# PCB_Schematic.net
KiCad netlist of a schematic drawn in Altium Designer
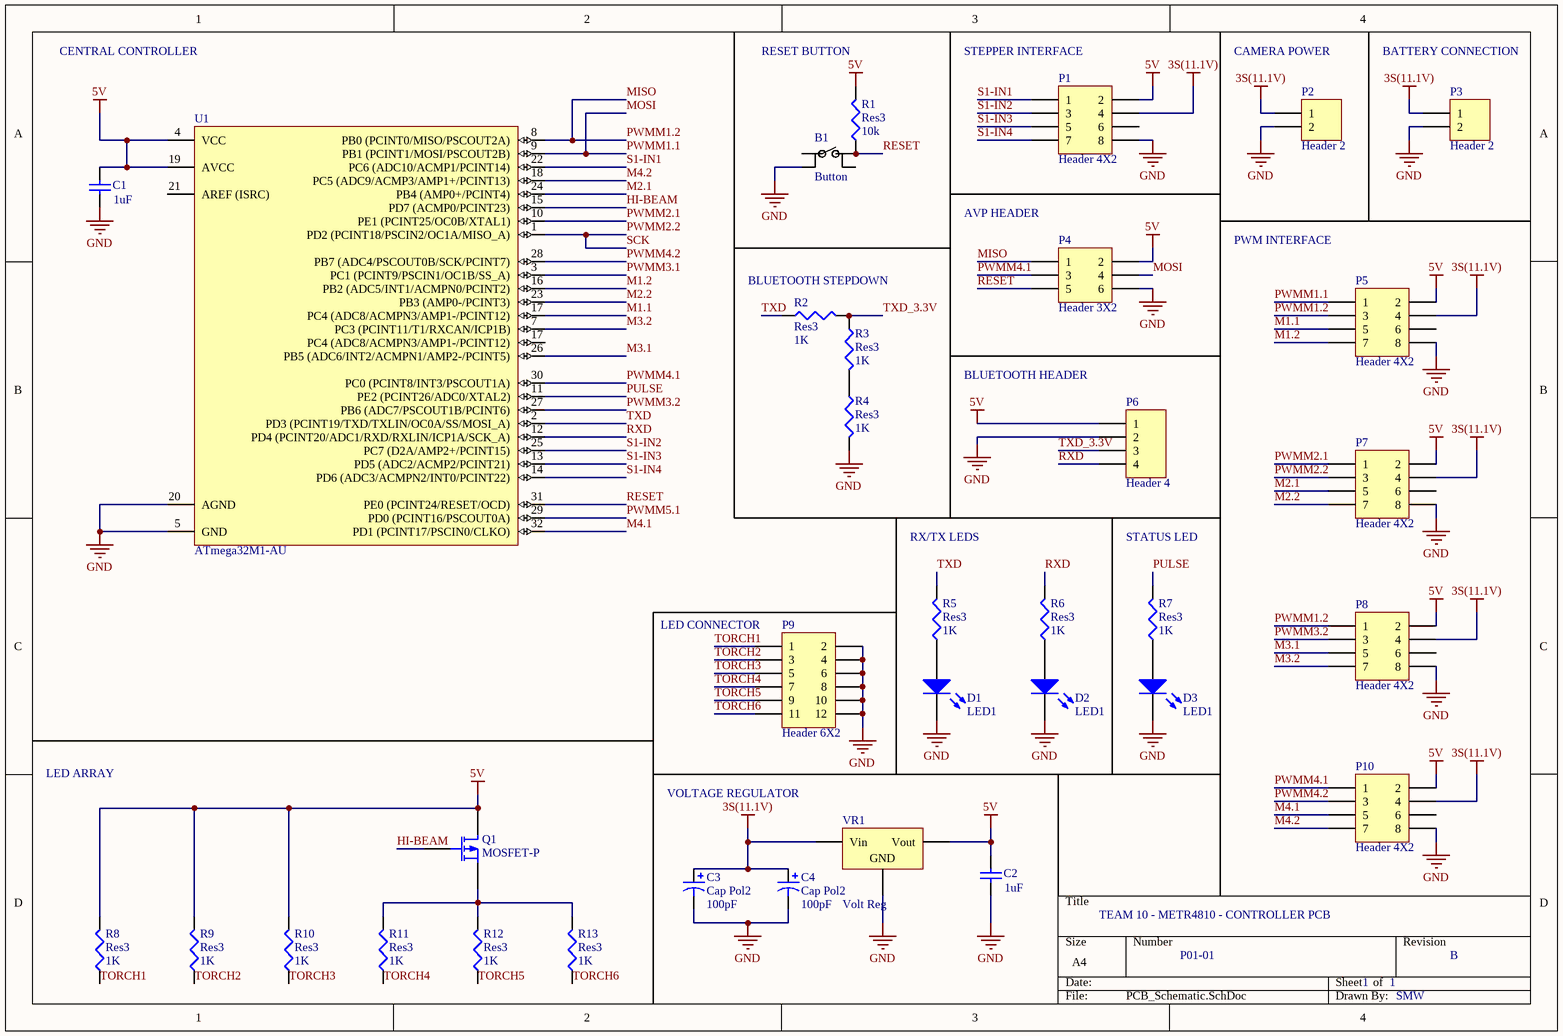
[diagram p0: PCB_Schematic.SchDoc]

(export (version "E")
  (design (tool "Eeschema 10.0.6"))
  (components
    (comp (ref "B1")
      (value "Button")
      (footprint "SMT Tactile Button")
      (libsource (lib "WillsSchematicLibrary") (part "Switch"))
    )
    (comp (ref "C1")
      (value "1uF")
      (footprint "1608[0603]")
      (description "Capacitor")
      (fields (field (name "Comment") "Cap") (field (name "PUBLISHER") "Altium Limited"))
      (libsource (lib "Miscellaneous Devices") (part "Cap"))
    )
    (comp (ref "C2")
      (value "1uF")
      (footprint "1608[0603]")
      (description "Capacitor")
      (fields (field (name "Comment") "Cap") (field (name "PUBLISHER") "Altium Limited"))
      (libsource (lib "Miscellaneous Devices") (part "Cap"))
    )
    (comp (ref "C3")
      (value "Cap Pol2")
      (footprint "CAPAE9983X105M")
      (description "Polarized Capacitor (Axial)")
      (fields (field (name "ALTIUM_VALUE") "100pF") (field (name "PUBLISHER") "Altium Limited"))
      (libsource (lib "Miscellaneous Devices") (part "Cap Pol2"))
    )
    (comp (ref "C4")
      (value "Cap Pol2")
      (footprint "CAPAE9983X105M")
      (description "Polarized Capacitor (Axial)")
      (fields (field (name "ALTIUM_VALUE") "100pF") (field (name "PUBLISHER") "Altium Limited"))
      (libsource (lib "Miscellaneous Devices") (part "Cap Pol2"))
    )
    (comp (ref "D1")
      (value "LED1")
      (footprint "L0603")
      (description "Typical RED GaAs LED")
      (fields (field (name "PUBLISHER") "Altium Limited"))
      (libsource (lib "Miscellaneous Devices") (part "LED1"))
    )
    (comp (ref "D2")
      (value "LED1")
      (footprint "L0603")
      (description "Typical RED GaAs LED")
      (fields (field (name "PUBLISHER") "Altium Limited"))
      (libsource (lib "Miscellaneous Devices") (part "LED1"))
    )
    (comp (ref "D3")
      (value "LED1")
      (footprint "L0603")
      (description "Typical RED GaAs LED")
      (fields (field (name "PUBLISHER") "Altium Limited"))
      (libsource (lib "Miscellaneous Devices") (part "LED1"))
    )
    (comp (ref "P1")
      (value "Header 4X2")
      (footprint "HDR2X4")
      (description "Header, 4-Pin, Dual row")
      (fields (field (name "PUBLISHER") "Altium Limited"))
      (libsource (lib "Miscellaneous Connectors") (part "Header 4X2"))
    )
    (comp (ref "P2")
      (value "Header 2")
      (footprint "HDR1X2")
      (description "Header, 2-Pin")
      (fields (field (name "PUBLISHER") "Altium Limited"))
      (libsource (lib "Miscellaneous Connectors") (part "Header 2"))
    )
    (comp (ref "P3")
      (value "Header 2")
      (footprint "HDR1X2")
      (description "Header, 2-Pin")
      (fields (field (name "PUBLISHER") "Altium Limited"))
      (libsource (lib "Miscellaneous Connectors") (part "Header 2"))
    )
    (comp (ref "P4")
      (value "Header 3X2")
      (footprint "HDR2X3")
      (description "Header, 3-Pin, Dual row")
      (fields (field (name "PUBLISHER") "Altium Limited"))
      (libsource (lib "Miscellaneous Connectors") (part "Header 3X2"))
    )
    (comp (ref "P5")
      (value "Header 4X2")
      (footprint "HDR2X4")
      (description "Header, 4-Pin, Dual row")
      (fields (field (name "PUBLISHER") "Altium Limited"))
      (libsource (lib "Miscellaneous Connectors") (part "Header 4X2"))
    )
    (comp (ref "P6")
      (value "Header 4")
      (footprint "HDR1X4")
      (description "Header, 4-Pin")
      (fields (field (name "PUBLISHER") "Altium Limited"))
      (libsource (lib "Miscellaneous Connectors") (part "Header 4"))
    )
    (comp (ref "P7")
      (value "Header 4X2")
      (footprint "HDR2X4")
      (description "Header, 4-Pin, Dual row")
      (fields (field (name "PUBLISHER") "Altium Limited"))
      (libsource (lib "Miscellaneous Connectors") (part "Header 4X2"))
    )
    (comp (ref "P8")
      (value "Header 4X2")
      (footprint "HDR2X4")
      (description "Header, 4-Pin, Dual row")
      (fields (field (name "PUBLISHER") "Altium Limited"))
      (libsource (lib "Miscellaneous Connectors") (part "Header 4X2"))
    )
    (comp (ref "P9")
      (value "Header 6X2")
      (footprint "HDR2X6")
      (description "Header, 6-Pin, Dual row")
      (fields (field (name "PUBLISHER") "Altium Limited"))
      (libsource (lib "Miscellaneous Connectors") (part "Header 6X2"))
    )
    (comp (ref "P10")
      (value "Header 4X2")
      (footprint "HDR2X4")
      (description "Header, 4-Pin, Dual row")
      (fields (field (name "PUBLISHER") "Altium Limited"))
      (libsource (lib "Miscellaneous Connectors") (part "Header 4X2"))
    )
    (comp (ref "Q1")
      (value "MOSFET-P")
      (footprint "SOT23-3")
      (description "P-Channel MOSFET")
      (fields (field (name "PUBLISHER") "Altium Limited"))
      (libsource (lib "Miscellaneous Devices") (part "MOSFET-P"))
    )
    (comp (ref "R1")
      (value "Res3")
      (footprint "J1-0603")
      (description "Resistor")
      (fields (field (name "ALTIUM_VALUE") "10k") (field (name "PUBLISHER") "Altium Limited"))
      (libsource (lib "Miscellaneous Devices") (part "Res3"))
    )
    (comp (ref "R2")
      (value "Res3")
      (footprint "J1-0603")
      (description "Resistor")
      (fields (field (name "ALTIUM_VALUE") "1K") (field (name "PUBLISHER") "Altium Limited"))
      (libsource (lib "Miscellaneous Devices") (part "Res3"))
    )
    (comp (ref "R3")
      (value "Res3")
      (footprint "J1-0603")
      (description "Resistor")
      (fields (field (name "ALTIUM_VALUE") "1K") (field (name "PUBLISHER") "Altium Limited"))
      (libsource (lib "Miscellaneous Devices") (part "Res3"))
    )
    (comp (ref "R4")
      (value "Res3")
      (footprint "J1-0603")
      (description "Resistor")
      (fields (field (name "ALTIUM_VALUE") "1K") (field (name "PUBLISHER") "Altium Limited"))
      (libsource (lib "Miscellaneous Devices") (part "Res3"))
    )
    (comp (ref "R5")
      (value "Res3")
      (footprint "J1-0603")
      (description "Resistor")
      (fields (field (name "ALTIUM_VALUE") "1K") (field (name "PUBLISHER") "Altium Limited"))
      (libsource (lib "Miscellaneous Devices") (part "Res3"))
    )
    (comp (ref "R6")
      (value "Res3")
      (footprint "J1-0603")
      (description "Resistor")
      (fields (field (name "ALTIUM_VALUE") "1K") (field (name "PUBLISHER") "Altium Limited"))
      (libsource (lib "Miscellaneous Devices") (part "Res3"))
    )
    (comp (ref "R7")
      (value "Res3")
      (footprint "J1-0603")
      (description "Resistor")
      (fields (field (name "ALTIUM_VALUE") "1K") (field (name "PUBLISHER") "Altium Limited"))
      (libsource (lib "Miscellaneous Devices") (part "Res3"))
    )
    (comp (ref "R8")
      (value "Res3")
      (footprint "J1-0603")
      (description "Resistor")
      (fields (field (name "ALTIUM_VALUE") "1K") (field (name "PUBLISHER") "Altium Limited"))
      (libsource (lib "Miscellaneous Devices") (part "Res3"))
    )
    (comp (ref "R9")
      (value "Res3")
      (footprint "J1-0603")
      (description "Resistor")
      (fields (field (name "ALTIUM_VALUE") "1K") (field (name "PUBLISHER") "Altium Limited"))
      (libsource (lib "Miscellaneous Devices") (part "Res3"))
    )
    (comp (ref "R10")
      (value "Res3")
      (footprint "J1-0603")
      (description "Resistor")
      (fields (field (name "ALTIUM_VALUE") "1K") (field (name "PUBLISHER") "Altium Limited"))
      (libsource (lib "Miscellaneous Devices") (part "Res3"))
    )
    (comp (ref "R11")
      (value "Res3")
      (footprint "J1-0603")
      (description "Resistor")
      (fields (field (name "ALTIUM_VALUE") "1K") (field (name "PUBLISHER") "Altium Limited"))
      (libsource (lib "Miscellaneous Devices") (part "Res3"))
    )
    (comp (ref "R12")
      (value "Res3")
      (footprint "J1-0603")
      (description "Resistor")
      (fields (field (name "ALTIUM_VALUE") "1K") (field (name "PUBLISHER") "Altium Limited"))
      (libsource (lib "Miscellaneous Devices") (part "Res3"))
    )
    (comp (ref "R13")
      (value "Res3")
      (footprint "J1-0603")
      (description "Resistor")
      (fields (field (name "ALTIUM_VALUE") "1K") (field (name "PUBLISHER") "Altium Limited"))
      (libsource (lib "Miscellaneous Devices") (part "Res3"))
    )
    (comp (ref "U1")
      (value "ATmega32M1-AU")
      (footprint "32A_L")
      (libsource (lib "Atmel Microcontroller AVR Automotive") (part "ATmega32M1-AU"))
    )
    (comp (ref "VR1")
      (value "Volt Reg")
      (footprint "D2PAK_N")
      (description "Voltage Regulator")
      (fields (field (name "PUBLISHER") "Altium Limited"))
      (libsource (lib "Miscellaneous Devices") (part "Volt Reg"))
    )
  )
  (nets
    (net (code "1") (name "/HI-BEAM") (class "Default")
      (node (ref "Q1") (pin "2") (pinfunction "G_2") (pintype "passive"))
      (node (ref "U1") (pin "15") (pinfunction "PD7_(ACMP0/PCINT23)_15") (pintype "bidirectional"))
    )
    (net (code "2") (name "/M1.1") (class "Default")
      (node (ref "P5") (pin "5") (pinfunction "5_5") (pintype "passive"))
      (node (ref "U1") (pin "17") (pinfunction "PC4_(ADC8/ACMPN3/AMP1-/PCINT12)_17") (pintype "bidirectional"))
    )
    (net (code "3") (name "/M1.2") (class "Default")
      (node (ref "P5") (pin "7") (pinfunction "7_7") (pintype "passive"))
      (node (ref "U1") (pin "16") (pinfunction "PB2_(ADC5/INT1/ACMPN0/PCINT2)_16") (pintype "bidirectional"))
    )
    (net (code "4") (name "/M2.1") (class "Default")
      (node (ref "P7") (pin "5") (pinfunction "5_5") (pintype "passive"))
      (node (ref "U1") (pin "24") (pinfunction "PB4_(AMP0+/PCINT4)_24") (pintype "bidirectional"))
    )
    (net (code "5") (name "/M2.2") (class "Default")
      (node (ref "P7") (pin "7") (pinfunction "7_7") (pintype "passive"))
      (node (ref "U1") (pin "23") (pinfunction "PB3_(AMP0-/PCINT3)_23") (pintype "bidirectional"))
    )
    (net (code "6") (name "/M3.1") (class "Default")
      (node (ref "P8") (pin "5") (pinfunction "5_5") (pintype "passive"))
      (node (ref "U1") (pin "26") (pinfunction "PB5_(ADC6/INT2/ACMPN1/AMP2-/PCINT5)_26") (pintype "bidirectional"))
    )
    (net (code "7") (name "/M3.2") (class "Default")
      (node (ref "P8") (pin "7") (pinfunction "7_7") (pintype "passive"))
      (node (ref "U1") (pin "7") (pinfunction "PC3_(PCINT11/T1/RXCAN/ICP1B)_7") (pintype "bidirectional"))
    )
    (net (code "8") (name "/M4.1") (class "Default")
      (node (ref "P10") (pin "5") (pinfunction "5_5") (pintype "passive"))
      (node (ref "U1") (pin "32") (pinfunction "PD1_(PCINT17/PSCIN0/CLKO)_32") (pintype "bidirectional"))
    )
    (net (code "9") (name "/M4.2") (class "Default")
      (node (ref "P10") (pin "7") (pinfunction "7_7") (pintype "passive"))
      (node (ref "U1") (pin "18") (pinfunction "PC5_(ADC9/ACMP3/AMP1+/PCINT13)_18") (pintype "bidirectional"))
    )
    (net (code "10") (name "/MISO") (class "Default")
      (node (ref "P4") (pin "1") (pinfunction "1_1") (pintype "passive"))
      (node (ref "P5") (pin "3") (pinfunction "3_3") (pintype "passive"))
      (node (ref "P8") (pin "1") (pinfunction "1_1") (pintype "passive"))
      (node (ref "U1") (pin "8") (pinfunction "PB0_(PCINT0/MISO/PSCOUT2A)_8") (pintype "bidirectional"))
    )
    (net (code "11") (name "/MOSI") (class "Default")
      (node (ref "P4") (pin "4") (pinfunction "4_4") (pintype "passive"))
      (node (ref "P5") (pin "1") (pinfunction "1_1") (pintype "passive"))
      (node (ref "U1") (pin "9") (pinfunction "PB1_(PCINT1/MOSI/PSCOUT2B)_9") (pintype "bidirectional"))
    )
    (net (code "12") (name "/PULSE") (class "Default")
      (node (ref "R7") (pin "2") (pinfunction "2_2") (pintype "passive"))
      (node (ref "U1") (pin "11") (pinfunction "PE2_(PCINT26/ADC0/XTAL2)_11") (pintype "bidirectional"))
    )
    (net (code "13") (name "/PWMM2.1") (class "Default")
      (node (ref "P7") (pin "1") (pinfunction "1_1") (pintype "passive"))
      (node (ref "U1") (pin "10") (pinfunction "PE1_(PCINT25/OC0B/XTAL1)_10") (pintype "bidirectional"))
    )
    (net (code "14") (name "/PWMM2.2") (class "Default")
      (node (ref "P7") (pin "3") (pinfunction "3_3") (pintype "passive"))
      (node (ref "U1") (pin "1") (pinfunction "PD2_(PCINT18/PSCIN2/OC1A/MISO_A)_1") (pintype "bidirectional"))
    )
    (net (code "15") (name "/PWMM3.1") (class "Default")
      (node (ref "U1") (pin "3") (pinfunction "PC1_(PCINT9/PSCIN1/OC1B/SS_A)_3") (pintype "bidirectional"))
    )
    (net (code "16") (name "/PWMM3.2") (class "Default")
      (node (ref "P8") (pin "3") (pinfunction "3_3") (pintype "passive"))
      (node (ref "U1") (pin "27") (pinfunction "PB6_(ADC7/PSCOUT1B/PCINT6)_27") (pintype "bidirectional"))
    )
    (net (code "17") (name "/PWMM4.1") (class "Default")
      (node (ref "P10") (pin "1") (pinfunction "1_1") (pintype "passive"))
      (node (ref "P4") (pin "3") (pinfunction "3_3") (pintype "passive"))
      (node (ref "U1") (pin "30") (pinfunction "PC0_(PCINT8/INT3/PSCOUT1A)_30") (pintype "bidirectional"))
    )
    (net (code "18") (name "/PWMM4.2") (class "Default")
      (node (ref "P10") (pin "3") (pinfunction "3_3") (pintype "passive"))
      (node (ref "U1") (pin "28") (pinfunction "PB7_(ADC4/PSCOUT0B/SCK/PCINT7)_28") (pintype "bidirectional"))
    )
    (net (code "19") (name "/PWMM5.1") (class "Default")
      (node (ref "U1") (pin "29") (pinfunction "PD0_(PCINT16/PSCOUT0A)_29") (pintype "bidirectional"))
    )
    (net (code "20") (name "/RESET") (class "Default")
      (node (ref "B1") (pin "4") (pinfunction "4_4") (pintype "passive"))
      (node (ref "P4") (pin "5") (pinfunction "5_5") (pintype "passive"))
      (node (ref "R1") (pin "1") (pinfunction "1_1") (pintype "passive"))
      (node (ref "U1") (pin "31") (pinfunction "PE0_(PCINT24/RESET/OCD)_31") (pintype "bidirectional"))
    )
    (net (code "21") (name "/RXD") (class "Default")
      (node (ref "P6") (pin "4") (pinfunction "4_4") (pintype "passive"))
      (node (ref "R6") (pin "2") (pinfunction "2_2") (pintype "passive"))
      (node (ref "U1") (pin "12") (pinfunction "PD4_(PCINT20/ADC1/RXD/RXLIN/ICP1A/SCK_A)_12") (pintype "bidirectional"))
    )
    (net (code "22") (name "/S1-IN1") (class "Default")
      (node (ref "P1") (pin "1") (pinfunction "1_1") (pintype "passive"))
      (node (ref "U1") (pin "22") (pinfunction "PC6_(ADC10/ACMP1/PCINT14)_22") (pintype "bidirectional"))
    )
    (net (code "23") (name "/S1-IN2") (class "Default")
      (node (ref "P1") (pin "3") (pinfunction "3_3") (pintype "passive"))
      (node (ref "U1") (pin "25") (pinfunction "PC7_(D2A/AMP2+/PCINT15)_25") (pintype "bidirectional"))
    )
    (net (code "24") (name "/S1-IN3") (class "Default")
      (node (ref "P1") (pin "5") (pinfunction "5_5") (pintype "passive"))
      (node (ref "U1") (pin "13") (pinfunction "PD5_(ADC2/ACMP2/PCINT21)_13") (pintype "bidirectional"))
    )
    (net (code "25") (name "/S1-IN4") (class "Default")
      (node (ref "P1") (pin "7") (pinfunction "7_7") (pintype "passive"))
      (node (ref "U1") (pin "14") (pinfunction "PD6_(ADC3/ACMPN2/INT0/PCINT22)_14") (pintype "bidirectional"))
    )
    (net (code "26") (name "/TORCH1") (class "Default")
      (node (ref "P9") (pin "1") (pinfunction "1_1") (pintype "passive"))
      (node (ref "R8") (pin "1") (pinfunction "1_1") (pintype "passive"))
    )
    (net (code "27") (name "/TORCH2") (class "Default")
      (node (ref "P9") (pin "3") (pinfunction "3_3") (pintype "passive"))
      (node (ref "R9") (pin "1") (pinfunction "1_1") (pintype "passive"))
    )
    (net (code "28") (name "/TORCH3") (class "Default")
      (node (ref "P9") (pin "5") (pinfunction "5_5") (pintype "passive"))
      (node (ref "R10") (pin "1") (pinfunction "1_1") (pintype "passive"))
    )
    (net (code "29") (name "/TORCH4") (class "Default")
      (node (ref "P9") (pin "7") (pinfunction "7_7") (pintype "passive"))
      (node (ref "R11") (pin "1") (pinfunction "1_1") (pintype "passive"))
    )
    (net (code "30") (name "/TORCH5") (class "Default")
      (node (ref "P9") (pin "9") (pinfunction "9_9") (pintype "passive"))
      (node (ref "R12") (pin "1") (pinfunction "1_1") (pintype "passive"))
    )
    (net (code "31") (name "/TORCH6") (class "Default")
      (node (ref "P9") (pin "11") (pinfunction "11_11") (pintype "passive"))
      (node (ref "R13") (pin "1") (pinfunction "1_1") (pintype "passive"))
    )
    (net (code "32") (name "/TXD") (class "Default")
      (node (ref "R2") (pin "1") (pinfunction "1_1") (pintype "passive"))
      (node (ref "R5") (pin "2") (pinfunction "2_2") (pintype "passive"))
      (node (ref "U1") (pin "2") (pinfunction "PD3_(PCINT19/TXD/TXLIN/OC0A/SS/MOSI_A)_2") (pintype "bidirectional"))
    )
    (net (code "33") (name "/TXD_3.3V") (class "Default")
      (node (ref "P6") (pin "3") (pinfunction "3_3") (pintype "passive"))
      (node (ref "R2") (pin "2") (pinfunction "2_2") (pintype "passive"))
      (node (ref "R3") (pin "1") (pinfunction "1_1") (pintype "passive"))
    )
    (net (code "34") (name "3S(11.1V)") (class "Default")
      (node (ref "C3") (pin "1") (pinfunction "1_1") (pintype "passive"))
      (node (ref "C4") (pin "1") (pinfunction "1_1") (pintype "passive"))
      (node (ref "P1") (pin "4") (pinfunction "4_4") (pintype "passive"))
      (node (ref "P10") (pin "4") (pinfunction "4_4") (pintype "passive"))
      (node (ref "P2") (pin "1") (pinfunction "1_1") (pintype "passive"))
      (node (ref "P3") (pin "1") (pinfunction "1_1") (pintype "passive"))
      (node (ref "P5") (pin "4") (pinfunction "4_4") (pintype "passive"))
      (node (ref "P7") (pin "4") (pinfunction "4_4") (pintype "passive"))
      (node (ref "P8") (pin "4") (pinfunction "4_4") (pintype "passive"))
      (node (ref "VR1") (pin "1") (pinfunction "Vin_1") (pintype "passive"))
    )
    (net (code "35") (name "5V") (class "Default")
      (node (ref "C1") (pin "2") (pinfunction "2_2") (pintype "passive"))
      (node (ref "C2") (pin "2") (pinfunction "2_2") (pintype "passive"))
      (node (ref "P1") (pin "2") (pinfunction "2_2") (pintype "passive"))
      (node (ref "P10") (pin "2") (pinfunction "2_2") (pintype "passive"))
      (node (ref "P4") (pin "2") (pinfunction "2_2") (pintype "passive"))
      (node (ref "P5") (pin "2") (pinfunction "2_2") (pintype "passive"))
      (node (ref "P6") (pin "1") (pinfunction "1_1") (pintype "passive"))
      (node (ref "P7") (pin "2") (pinfunction "2_2") (pintype "passive"))
      (node (ref "P8") (pin "2") (pinfunction "2_2") (pintype "passive"))
      (node (ref "Q1") (pin "1") (pinfunction "D_1") (pintype "passive"))
      (node (ref "R1") (pin "2") (pinfunction "2_2") (pintype "passive"))
      (node (ref "R10") (pin "2") (pinfunction "2_2") (pintype "passive"))
      (node (ref "R8") (pin "2") (pinfunction "2_2") (pintype "passive"))
      (node (ref "R9") (pin "2") (pinfunction "2_2") (pintype "passive"))
      (node (ref "U1") (pin "19") (pinfunction "AVCC_19") (pintype "power_in"))
      (node (ref "U1") (pin "4") (pinfunction "VCC_4") (pintype "power_in"))
      (node (ref "VR1") (pin "3") (pinfunction "Vout_3") (pintype "passive"))
    )
    (net (code "36") (name "GND") (class "Default")
      (node (ref "B1") (pin "2") (pinfunction "2_2") (pintype "passive"))
      (node (ref "C1") (pin "1") (pinfunction "1_1") (pintype "passive"))
      (node (ref "C2") (pin "1") (pinfunction "1_1") (pintype "passive"))
      (node (ref "C3") (pin "2") (pinfunction "2_2") (pintype "passive"))
      (node (ref "C4") (pin "2") (pinfunction "2_2") (pintype "passive"))
      (node (ref "D1") (pin "2") (pinfunction "K_2") (pintype "passive"))
      (node (ref "D2") (pin "2") (pinfunction "K_2") (pintype "passive"))
      (node (ref "D3") (pin "2") (pinfunction "K_2") (pintype "passive"))
      (node (ref "P1") (pin "8") (pinfunction "8_8") (pintype "passive"))
      (node (ref "P10") (pin "8") (pinfunction "8_8") (pintype "passive"))
      (node (ref "P2") (pin "2") (pinfunction "2_2") (pintype "passive"))
      (node (ref "P3") (pin "2") (pinfunction "2_2") (pintype "passive"))
      (node (ref "P4") (pin "6") (pinfunction "6_6") (pintype "passive"))
      (node (ref "P5") (pin "8") (pinfunction "8_8") (pintype "passive"))
      (node (ref "P6") (pin "2") (pinfunction "2_2") (pintype "passive"))
      (node (ref "P7") (pin "8") (pinfunction "8_8") (pintype "passive"))
      (node (ref "P8") (pin "8") (pinfunction "8_8") (pintype "passive"))
      (node (ref "P9") (pin "10") (pinfunction "10_10") (pintype "passive"))
      (node (ref "P9") (pin "12") (pinfunction "12_12") (pintype "passive"))
      (node (ref "P9") (pin "2") (pinfunction "2_2") (pintype "passive"))
      (node (ref "P9") (pin "4") (pinfunction "4_4") (pintype "passive"))
      (node (ref "P9") (pin "6") (pinfunction "6_6") (pintype "passive"))
      (node (ref "P9") (pin "8") (pinfunction "8_8") (pintype "passive"))
      (node (ref "R4") (pin "2") (pinfunction "2_2") (pintype "passive"))
      (node (ref "U1") (pin "20") (pinfunction "AGND_20") (pintype "power_in"))
      (node (ref "U1") (pin "5") (pinfunction "GND_5") (pintype "power_in"))
      (node (ref "VR1") (pin "2") (pinfunction "GND_2") (pintype "passive"))
    )
    (net (code "37") (name "Net-(D1-A)") (class "Default")
      (node (ref "D1") (pin "1") (pinfunction "A_1") (pintype "passive"))
      (node (ref "R5") (pin "1") (pinfunction "1_1") (pintype "passive"))
    )
    (net (code "38") (name "Net-(D2-A)") (class "Default")
      (node (ref "D2") (pin "1") (pinfunction "A_1") (pintype "passive"))
      (node (ref "R6") (pin "1") (pinfunction "1_1") (pintype "passive"))
    )
    (net (code "39") (name "Net-(D3-A)") (class "Default")
      (node (ref "D3") (pin "1") (pinfunction "A_1") (pintype "passive"))
      (node (ref "R7") (pin "1") (pinfunction "1_1") (pintype "passive"))
    )
    (net (code "40") (name "Net-(Q1-S)") (class "Default")
      (node (ref "Q1") (pin "3") (pinfunction "S_3") (pintype "passive"))
      (node (ref "R11") (pin "2") (pinfunction "2_2") (pintype "passive"))
      (node (ref "R12") (pin "2") (pinfunction "2_2") (pintype "passive"))
      (node (ref "R13") (pin "2") (pinfunction "2_2") (pintype "passive"))
    )
    (net (code "41") (name "Net-(R3-Pad2)") (class "Default")
      (node (ref "R3") (pin "2") (pinfunction "2_2") (pintype "passive"))
      (node (ref "R4") (pin "1") (pinfunction "1_1") (pintype "passive"))
    )
    (net (code "42") (name "unconnected-(B1-Pad1)") (class "Default")
      (node (ref "B1") (pin "1") (pinfunction "1_1") (pintype "passive"))
    )
    (net (code "43") (name "unconnected-(B1-Pad3)") (class "Default")
      (node (ref "B1") (pin "3") (pinfunction "3_3") (pintype "passive"))
    )
    (net (code "44") (name "unconnected-(P1-Pad6)") (class "Default")
      (node (ref "P1") (pin "6") (pinfunction "6_6") (pintype "passive"))
    )
    (net (code "45") (name "unconnected-(P5-Pad6)") (class "Default")
      (node (ref "P5") (pin "6") (pinfunction "6_6") (pintype "passive"))
    )
    (net (code "46") (name "unconnected-(P7-Pad6)") (class "Default")
      (node (ref "P7") (pin "6") (pinfunction "6_6") (pintype "passive"))
    )
    (net (code "47") (name "unconnected-(P8-Pad6)") (class "Default")
      (node (ref "P8") (pin "6") (pinfunction "6_6") (pintype "passive"))
    )
    (net (code "48") (name "unconnected-(P10-Pad6)") (class "Default")
      (node (ref "P10") (pin "6") (pinfunction "6_6") (pintype "passive"))
    )
    (net (code "49") (name "unconnected-(U1-AREF_(ISRC)-Pad21)") (class "Default")
      (node (ref "U1") (pin "21") (pinfunction "AREF_(ISRC)_21") (pintype "power_in"))
    )
    (net (code "50") (name "unconnected-(U1-PC4_(ADC8{slash}ACMPN3{slash}AMP1-{slash}PCINT12)-Pad17)") (class "Default")
      (node (ref "U1") (pin "17") (pinfunction "PC4_(ADC8/ACMPN3/AMP1-/PCINT12)_17") (pintype "bidirectional"))
    )
  )
)
